# cuisinart-oven.net
KiCad netlist of a schematic drawn in EAGLE
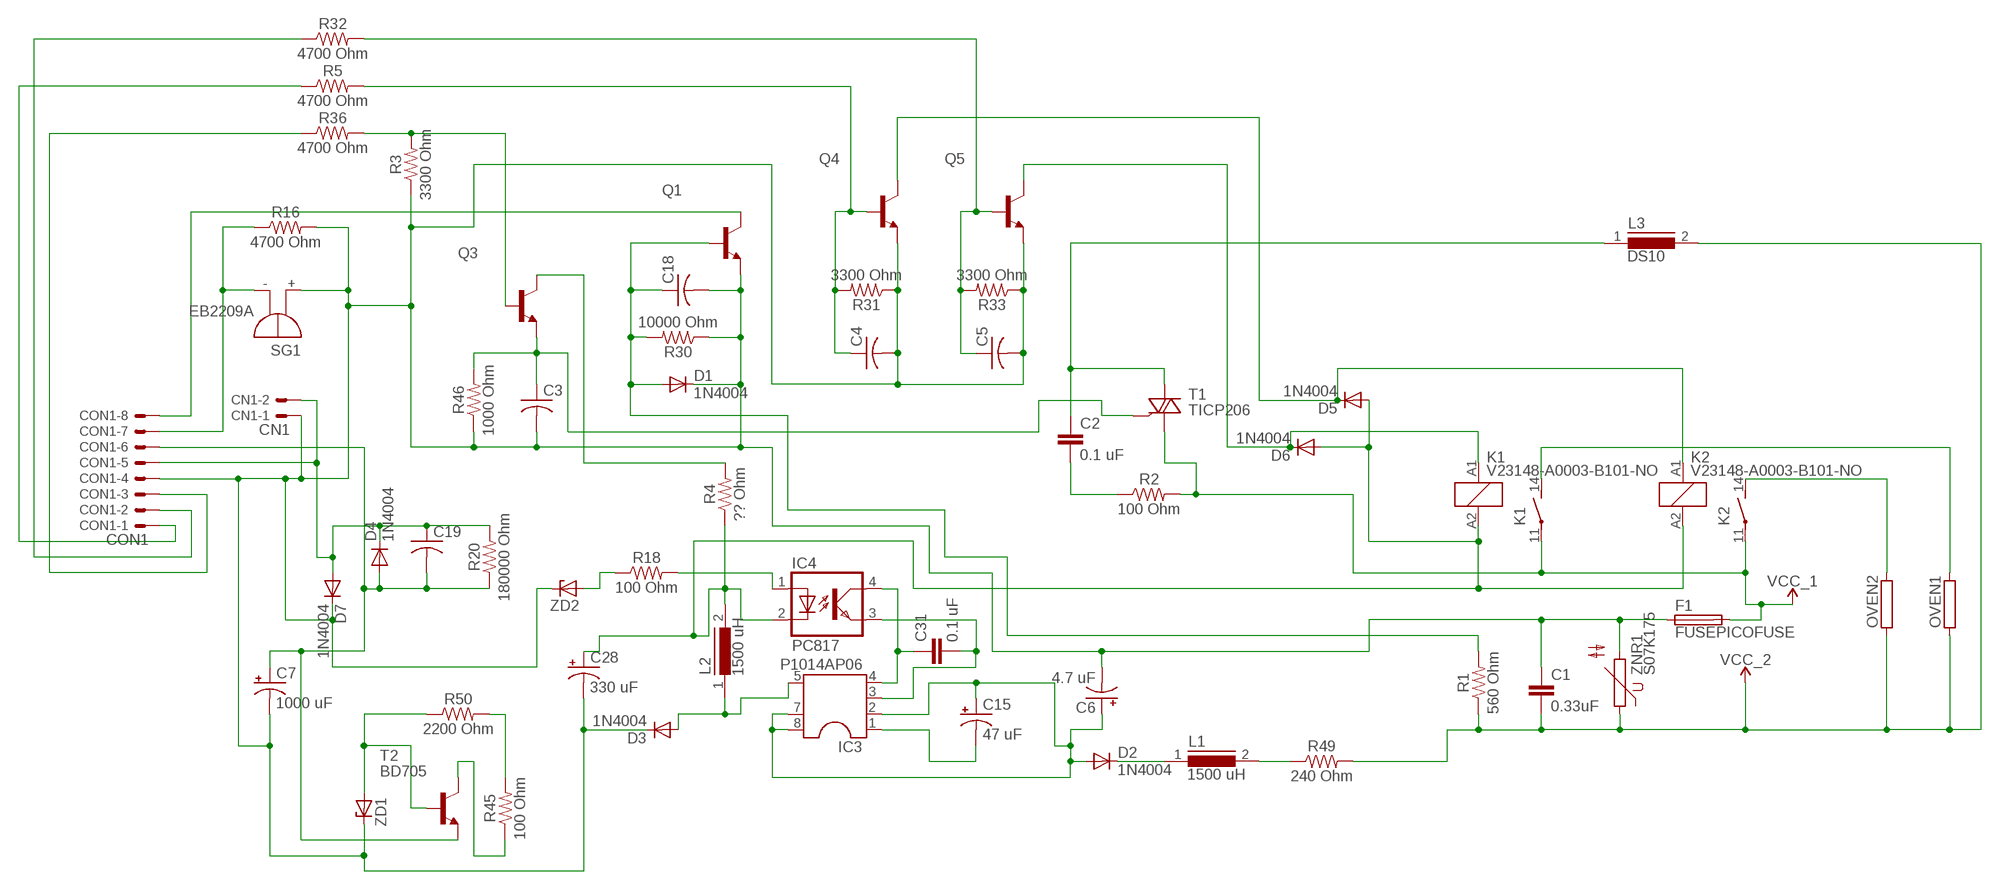
[diagram p0: schematic, sheet 1]

(export (version "E")
  (design (tool "Eeschema 10.0.6"))
  (components
    (comp (ref "C1")
      (value "0.33uF")
      (footprint "eagle-import:C15B9")
      (libsource (lib "eagle-import") (part "C15/9"))
    )
    (comp (ref "C2")
      (value "0.1 uF")
      (footprint "eagle-import:XC15B6")
      (libsource (lib "eagle-import") (part "CXXC15B6"))
    )
    (comp (ref "C3")
      (value "C-US025-024X044")
      (footprint "eagle-import:C025-024X044")
      (libsource (lib "eagle-import") (part "C-US025-024X044"))
    )
    (comp (ref "C4")
      (value "C-US025-024X044")
      (footprint "eagle-import:C025-024X044")
      (libsource (lib "eagle-import") (part "C-US025-024X044"))
    )
    (comp (ref "C5")
      (value "C-US025-024X044")
      (footprint "eagle-import:C025-024X044")
      (libsource (lib "eagle-import") (part "C-US025-024X044"))
    )
    (comp (ref "C6")
      (value "4.7 uF")
      (footprint "eagle-import:E3,5-8")
      (libsource (lib "eagle-import") (part "CPOL-USE3.5-8"))
    )
    (comp (ref "C7")
      (value "1000 uF")
      (footprint "eagle-import:E3,5-8")
      (libsource (lib "eagle-import") (part "CPOL-USE3.5-8"))
    )
    (comp (ref "C15")
      (value "47 uF")
      (footprint "eagle-import:E2-5")
      (libsource (lib "eagle-import") (part "CPOL-USE2-5"))
    )
    (comp (ref "C18")
      (value "C-US025-024X044")
      (footprint "eagle-import:C025-024X044")
      (libsource (lib "eagle-import") (part "C-US025-024X044"))
    )
    (comp (ref "C19")
      (value "C-US025-024X044")
      (footprint "eagle-import:C025-024X044")
      (libsource (lib "eagle-import") (part "C-US025-024X044"))
    )
    (comp (ref "C28")
      (value "330 uF")
      (footprint "eagle-import:E3,5-10")
      (libsource (lib "eagle-import") (part "CPOL-USE3.5-10"))
    )
    (comp (ref "C31")
      (value "0.1 uF")
      (footprint "eagle-import:XC15B6")
      (libsource (lib "eagle-import") (part "CXXC15B6"))
    )
    (comp (ref "CN1")
      (value "CN1")
      (footprint "eagle-import:22-23-2021")
      (fields (field (name "MF") "MOLEX") (field (name "MPN") "22-23-2021"))
      (libsource (lib "eagle-import") (part "22-23-2021"))
    )
    (comp (ref "CON1")
      (value "CON1")
      (footprint "eagle-import:22-23-2081")
      (fields (field (name "MF") "MOLEX") (field (name "MPN") "22-23-2081"))
      (libsource (lib "eagle-import") (part "22-23-2081"))
    )
    (comp (ref "D1")
      (value "1N4004")
      (footprint "eagle-import:DO41-10")
      (libsource (lib "eagle-import") (part "1N4004"))
    )
    (comp (ref "D2")
      (value "1N4004")
      (footprint "eagle-import:DO41-10")
      (libsource (lib "eagle-import") (part "1N4004"))
    )
    (comp (ref "D3")
      (value "1N4004")
      (footprint "eagle-import:DO41-10")
      (libsource (lib "eagle-import") (part "1N4004"))
    )
    (comp (ref "D4")
      (value "1N4004")
      (footprint "eagle-import:DO41-10")
      (libsource (lib "eagle-import") (part "1N4004"))
    )
    (comp (ref "D5")
      (value "1N4004")
      (footprint "eagle-import:DO41-10")
      (libsource (lib "eagle-import") (part "1N4004"))
    )
    (comp (ref "D6")
      (value "1N4004")
      (footprint "eagle-import:DO41-10")
      (libsource (lib "eagle-import") (part "1N4004"))
    )
    (comp (ref "D7")
      (value "1N4004")
      (footprint "eagle-import:DO41-10")
      (libsource (lib "eagle-import") (part "1N4004"))
    )
    (comp (ref "F1")
      (value "FUSEPICOFUSE")
      (footprint "eagle-import:PICOFUSE")
      (libsource (lib "eagle-import") (part "FUSEPICOFUSE"))
    )
    (comp (ref "IC3")
      (value "P1014AP06")
      (footprint "eagle-import:DIP-8B")
      (libsource (lib "eagle-import") (part "TNY267PN"))
    )
    (comp (ref "IC4")
      (value "PC817")
      (footprint "eagle-import:DIL04")
      (fields (field (name "MPN") "PC817X4J000F"))
      (libsource (lib "eagle-import") (part "PC817"))
    )
    (comp (ref "K1")
      (value "V23148-A0003-B101-NO")
      (footprint "eagle-import:V23148-NO")
      (fields (field (name "MPN") "V23148-A0007-A101"))
      (libsource (lib "eagle-import") (part "V23148--NOA0003-B101"))
    )
    (comp (ref "K2")
      (value "V23148-A0003-B101-NO")
      (footprint "eagle-import:V23148-NO")
      (fields (field (name "MPN") "V23148-A0007-A101"))
      (libsource (lib "eagle-import") (part "V23148--NOA0003-B101"))
    )
    (comp (ref "L1")
      (value "1500 uH")
      (footprint "eagle-import:82114R")
      (libsource (lib "eagle-import") (part "82114R"))
    )
    (comp (ref "L2")
      (value "1500 uH")
      (footprint "eagle-import:82114R")
      (libsource (lib "eagle-import") (part "82114R"))
    )
    (comp (ref "L3")
      (value "DS10")
      (footprint "eagle-import:DS10")
      (libsource (lib "eagle-import") (part "DS10"))
    )
    (comp (ref "OVEN1")
      (value "RRWM10X65")
      (footprint "eagle-import:RWM10X65")
      (libsource (lib "eagle-import") (part "RRWM10X65"))
    )
    (comp (ref "OVEN2")
      (value "RRWM10X65")
      (footprint "eagle-import:RWM10X65")
      (libsource (lib "eagle-import") (part "RRWM10X65"))
    )
    (comp (ref "Q1")
      (value "BFS17-NPN-SOT23-BEC")
      (footprint "eagle-import:SOT23-BEC")
      (libsource (lib "eagle-import") (part "-NPN-SOT23-BECBFS17"))
    )
    (comp (ref "Q3")
      (value "BFS17-NPN-SOT23-BEC")
      (footprint "eagle-import:SOT23-BEC")
      (libsource (lib "eagle-import") (part "-NPN-SOT23-BECBFS17"))
    )
    (comp (ref "Q4")
      (value "BFS17-NPN-SOT23-BEC")
      (footprint "eagle-import:SOT23-BEC")
      (libsource (lib "eagle-import") (part "-NPN-SOT23-BECBFS17"))
    )
    (comp (ref "Q5")
      (value "BFS17-NPN-SOT23-BEC")
      (footprint "eagle-import:SOT23-BEC")
      (libsource (lib "eagle-import") (part "-NPN-SOT23-BECBFS17"))
    )
    (comp (ref "R1")
      (value "560 Ohm")
      (footprint "eagle-import:AXIAL-0.3")
      (libsource (lib "eagle-import") (part "RESISTORAXIAL-0.3"))
    )
    (comp (ref "R2")
      (value "100 Ohm")
      (footprint "eagle-import:AXIAL-0.3")
      (libsource (lib "eagle-import") (part "RESISTORAXIAL-0.3"))
    )
    (comp (ref "R3")
      (value "3300 Ohm")
      (footprint "eagle-import:AXIAL-0.3")
      (libsource (lib "eagle-import") (part "RESISTORAXIAL-0.3"))
    )
    (comp (ref "R4")
      (value "?? Ohm")
      (footprint "eagle-import:AXIAL-0.3")
      (libsource (lib "eagle-import") (part "RESISTORAXIAL-0.3"))
    )
    (comp (ref "R5")
      (value "4700 Ohm")
      (footprint "eagle-import:AXIAL-0.3")
      (libsource (lib "eagle-import") (part "RESISTORAXIAL-0.3"))
    )
    (comp (ref "R16")
      (value "4700 Ohm")
      (footprint "eagle-import:AXIAL-0.3")
      (libsource (lib "eagle-import") (part "RESISTORAXIAL-0.3"))
    )
    (comp (ref "R18")
      (value "100 Ohm")
      (footprint "eagle-import:AXIAL-0.3")
      (libsource (lib "eagle-import") (part "RESISTORAXIAL-0.3"))
    )
    (comp (ref "R20")
      (value "180000 Ohm")
      (footprint "eagle-import:AXIAL-0.3")
      (libsource (lib "eagle-import") (part "RESISTORAXIAL-0.3"))
    )
    (comp (ref "R30")
      (value "10000 Ohm")
      (footprint "eagle-import:AXIAL-0.3")
      (libsource (lib "eagle-import") (part "RESISTORAXIAL-0.3"))
    )
    (comp (ref "R31")
      (value "3300 Ohm")
      (footprint "eagle-import:AXIAL-0.3")
      (libsource (lib "eagle-import") (part "RESISTORAXIAL-0.3"))
    )
    (comp (ref "R32")
      (value "4700 Ohm")
      (footprint "eagle-import:AXIAL-0.3")
      (libsource (lib "eagle-import") (part "RESISTORAXIAL-0.3"))
    )
    (comp (ref "R33")
      (value "3300 Ohm")
      (footprint "eagle-import:AXIAL-0.3")
      (libsource (lib "eagle-import") (part "RESISTORAXIAL-0.3"))
    )
    (comp (ref "R36")
      (value "4700 Ohm")
      (footprint "eagle-import:AXIAL-0.3")
      (libsource (lib "eagle-import") (part "RESISTORAXIAL-0.3"))
    )
    (comp (ref "R45")
      (value "100 Ohm")
      (footprint "eagle-import:AXIAL-0.3")
      (libsource (lib "eagle-import") (part "RESISTORAXIAL-0.3"))
    )
    (comp (ref "R46")
      (value "1000 Ohm")
      (footprint "eagle-import:AXIAL-0.3")
      (libsource (lib "eagle-import") (part "RESISTORAXIAL-0.3"))
    )
    (comp (ref "R49")
      (value "240 Ohm")
      (footprint "eagle-import:AXIAL-0.3")
      (libsource (lib "eagle-import") (part "RESISTORAXIAL-0.3"))
    )
    (comp (ref "R50")
      (value "2200 Ohm")
      (footprint "eagle-import:AXIAL-0.3")
      (libsource (lib "eagle-import") (part "RESISTORAXIAL-0.3"))
    )
    (comp (ref "SG1")
      (value "EB2209A")
      (footprint "eagle-import:EB2209A")
      (libsource (lib "eagle-import") (part "EB2209A"))
    )
    (comp (ref "T1")
      (value "TICP206")
      (footprint "eagle-import:TO92-6")
      (libsource (lib "eagle-import") (part "TICP206"))
    )
    (comp (ref "T2")
      (value "BD705")
      (footprint "eagle-import:TO220")
      (libsource (lib "eagle-import") (part "BD705"))
    )
    (comp (ref "ZD1")
      (value "ZENER_DIODEDO41Z10")
      (footprint "eagle-import:DO41Z10")
      (libsource (lib "eagle-import") (part "ZENER_DIODEDO41Z10"))
    )
    (comp (ref "ZD2")
      (value "ZENER_DIODEDO41Z10")
      (footprint "eagle-import:DO41Z10")
      (libsource (lib "eagle-import") (part "ZENER_DIODEDO41Z10"))
    )
    (comp (ref "ZNR1")
      (value "S07K175")
      (footprint "eagle-import:S07K175")
      (libsource (lib "eagle-import") (part "S07K175"))
    )
  )
  (nets
    (net (code "1") (name "Net-(C2-Pad1)") (class "Default")
      (node (ref "C2") (pin "1") (pinfunction "1_1") (pintype "passive"))
      (node (ref "L3") (pin "1") (pinfunction "1_1") (pintype "passive"))
      (node (ref "T1") (pin "A2") (pinfunction "A2_A2") (pintype "passive"))
    )
    (net (code "2") (name "Net-(CN1A-S)") (class "Default")
      (node (ref "C1") (pin "1") (pinfunction "1_1") (pintype "passive"))
      (node (ref "C18") (pin "2") (pinfunction "2_2") (pintype "passive"))
      (node (ref "C28") (pin "-") (pinfunction "-_-") (pintype "passive"))
      (node (ref "C3") (pin "2") (pinfunction "2_2") (pintype "passive"))
      (node (ref "C4") (pin "2") (pinfunction "2_2") (pintype "passive"))
      (node (ref "C5") (pin "2") (pinfunction "2_2") (pintype "passive"))
      (node (ref "C6") (pin "-") (pinfunction "-_-") (pintype "passive"))
      (node (ref "C7") (pin "-") (pinfunction "-_-") (pintype "passive"))
      (node (ref "CN1") (pin "1") (pinfunction "S_1") (pintype "passive"))
      (node (ref "CON1") (pin "4") (pinfunction "S_4") (pintype "passive"))
      (node (ref "D1") (pin "C") (pinfunction "C_C") (pintype "passive"))
      (node (ref "D3") (pin "C") (pinfunction "C_C") (pintype "passive"))
      (node (ref "D7") (pin "C") (pinfunction "C_C") (pintype "passive"))
      (node (ref "F1") (pin "1") (pinfunction "1_1") (pintype "passive"))
      (node (ref "Q1") (pin "E") (pinfunction "E_E") (pintype "passive"))
      (node (ref "Q4") (pin "E") (pinfunction "E_E") (pintype "passive"))
      (node (ref "Q5") (pin "E") (pinfunction "E_E") (pintype "passive"))
      (node (ref "R16") (pin "P$2") (pinfunction "2_P$2") (pintype "passive"))
      (node (ref "R3") (pin "P$1") (pinfunction "1_P$1") (pintype "passive"))
      (node (ref "R30") (pin "P$1") (pinfunction "1_P$1") (pintype "passive"))
      (node (ref "R31") (pin "P$1") (pinfunction "1_P$1") (pintype "passive"))
      (node (ref "R33") (pin "P$1") (pinfunction "1_P$1") (pintype "passive"))
      (node (ref "R46") (pin "P$1") (pinfunction "1_P$1") (pintype "passive"))
      (node (ref "SG1") (pin "+") (pinfunction "+_+") (pintype "passive"))
      (node (ref "ZD1") (pin "C") (pinfunction "CATHODE_C") (pintype "passive"))
      (node (ref "ZD2") (pin "C") (pinfunction "CATHODE_C") (pintype "passive"))
      (node (ref "ZNR1") (pin "2") (pinfunction "2_2") (pintype "passive"))
    )
    (net (code "3") (name "Net-(CN1B-S)") (class "Default")
      (node (ref "C19") (pin "1") (pinfunction "1_1") (pintype "passive"))
      (node (ref "CN1") (pin "2") (pinfunction "S_2") (pintype "passive"))
      (node (ref "CON1") (pin "5") (pinfunction "S_5") (pintype "passive"))
      (node (ref "D4") (pin "C") (pinfunction "C_C") (pintype "passive"))
      (node (ref "D7") (pin "A") (pinfunction "A_A") (pintype "passive"))
      (node (ref "R20") (pin "P$2") (pinfunction "2_P$2") (pintype "passive"))
    )
    (net (code "4") (name "Net-(CON1A-S)") (class "Default")
      (node (ref "CON1") (pin "1") (pinfunction "S_1") (pintype "passive"))
      (node (ref "R5") (pin "P$1") (pinfunction "1_P$1") (pintype "passive"))
    )
    (net (code "5") (name "Net-(CON1B-S)") (class "Default")
      (node (ref "CON1") (pin "2") (pinfunction "S_2") (pintype "passive"))
      (node (ref "R32") (pin "P$1") (pinfunction "1_P$1") (pintype "passive"))
    )
    (net (code "6") (name "Net-(CON1C-S)") (class "Default")
      (node (ref "CON1") (pin "3") (pinfunction "S_3") (pintype "passive"))
      (node (ref "R36") (pin "P$1") (pinfunction "1_P$1") (pintype "passive"))
    )
    (net (code "7") (name "Net-(CON1F-S)") (class "Default")
      (node (ref "C19") (pin "2") (pinfunction "2_2") (pintype "passive"))
      (node (ref "C7") (pin "+") (pinfunction "+_+") (pintype "passive"))
      (node (ref "CON1") (pin "6") (pinfunction "S_6") (pintype "passive"))
      (node (ref "D4") (pin "A") (pinfunction "A_A") (pintype "passive"))
      (node (ref "R20") (pin "P$1") (pinfunction "1_P$1") (pintype "passive"))
      (node (ref "T2") (pin "3") (pinfunction "E_3") (pintype "passive"))
    )
    (net (code "8") (name "Net-(CON1G-S)") (class "Default")
      (node (ref "CON1") (pin "7") (pinfunction "S_7") (pintype "passive"))
      (node (ref "R16") (pin "P$1") (pinfunction "1_P$1") (pintype "passive"))
      (node (ref "SG1") (pin "-") (pinfunction "-_-") (pintype "passive"))
    )
    (net (code "9") (name "Net-(CON1H-S)") (class "Default")
      (node (ref "CON1") (pin "8") (pinfunction "S_8") (pintype "passive"))
      (node (ref "Q1") (pin "C") (pinfunction "C_C") (pintype "passive"))
    )
    (net (code "10") (name "Net-(D2-PadC)") (class "Default")
      (node (ref "D2") (pin "C") (pinfunction "C_C") (pintype "passive"))
      (node (ref "L1") (pin "1") (pinfunction "1_1") (pintype "passive"))
    )
    (net (code "11") (name "Net-(IC3-2GND)") (class "Default")
      (node (ref "C15") (pin "+") (pinfunction "+_+") (pintype "passive"))
      (node (ref "C6") (pin "+") (pinfunction "+_+") (pintype "passive"))
      (node (ref "D2") (pin "A") (pinfunction "A_A") (pintype "passive"))
      (node (ref "IC3") (pin "2") (pinfunction "2GND_2") (pintype "passive"))
      (node (ref "IC3") (pin "7") (pinfunction "7HV-GND_7") (pintype "passive"))
      (node (ref "IC3") (pin "8") (pinfunction "8HV-GND_8") (pintype "passive"))
    )
    (net (code "12") (name "Net-(IC3-3GND)") (class "Default")
      (node (ref "C31") (pin "2") (pinfunction "2_2") (pintype "passive"))
      (node (ref "IC3") (pin "3") (pinfunction "3GND_3") (pintype "passive"))
      (node (ref "IC4") (pin "3") (pinfunction "EMIT_3") (pintype "passive"))
    )
    (net (code "13") (name "Net-(IC3-BP)") (class "Default")
      (node (ref "C15") (pin "-") (pinfunction "-_-") (pintype "passive"))
      (node (ref "IC3") (pin "1") (pinfunction "BP_1") (pintype "passive"))
    )
    (net (code "14") (name "Net-(IC3-D)") (class "Default")
      (node (ref "D3") (pin "A") (pinfunction "A_A") (pintype "passive"))
      (node (ref "IC3") (pin "5") (pinfunction "D_5") (pintype "passive"))
      (node (ref "L2") (pin "1") (pinfunction "1_1") (pintype "passive"))
    )
    (net (code "15") (name "Net-(IC3-EN{slash}UV)") (class "Default")
      (node (ref "C31") (pin "1") (pinfunction "1_1") (pintype "passive"))
      (node (ref "IC3") (pin "4") (pinfunction "EN/UV_4") (pintype "passive"))
      (node (ref "IC4") (pin "4") (pinfunction "COL_4") (pintype "passive"))
    )
    (net (code "16") (name "Net-(IC4-A)") (class "Default")
      (node (ref "IC4") (pin "1") (pinfunction "A_1") (pintype "passive"))
      (node (ref "R18") (pin "P$2") (pinfunction "2_P$2") (pintype "passive"))
    )
    (net (code "17") (name "Net-(IC4-C)") (class "Default")
      (node (ref "C28") (pin "+") (pinfunction "+_+") (pintype "passive"))
      (node (ref "D5") (pin "A") (pinfunction "A_A") (pintype "passive"))
      (node (ref "D6") (pin "A") (pinfunction "A_A") (pintype "passive"))
      (node (ref "IC4") (pin "2") (pinfunction "C_2") (pintype "passive"))
      (node (ref "K1") (pin "A2") (pinfunction "2_A2") (pintype "passive"))
      (node (ref "K2") (pin "A2") (pinfunction "2_A2") (pintype "passive"))
      (node (ref "L2") (pin "2") (pinfunction "2_2") (pintype "passive"))
      (node (ref "R4") (pin "P$1") (pinfunction "1_P$1") (pintype "passive"))
    )
    (net (code "18") (name "Net-(K1A-1)") (class "Default")
      (node (ref "D6") (pin "C") (pinfunction "C_C") (pintype "passive"))
      (node (ref "K1") (pin "A1") (pinfunction "1_A1") (pintype "passive"))
      (node (ref "Q5") (pin "C") (pinfunction "C_C") (pintype "passive"))
    )
    (net (code "19") (name "Net-(K1B-S)") (class "Default")
      (node (ref "K1") (pin "14") (pinfunction "S_14") (pintype "passive"))
      (node (ref "OVEN1") (pin "2") (pinfunction "2_2") (pintype "passive"))
    )
    (net (code "20") (name "Net-(K2A-1)") (class "Default")
      (node (ref "D5") (pin "C") (pinfunction "C_C") (pintype "passive"))
      (node (ref "K2") (pin "A1") (pinfunction "1_A1") (pintype "passive"))
      (node (ref "Q4") (pin "C") (pinfunction "C_C") (pintype "passive"))
    )
    (net (code "21") (name "Net-(K2B-S)") (class "Default")
      (node (ref "K2") (pin "14") (pinfunction "S_14") (pintype "passive"))
      (node (ref "OVEN2") (pin "2") (pinfunction "2_2") (pintype "passive"))
    )
    (net (code "22") (name "Net-(R1-2)") (class "Default")
      (node (ref "C18") (pin "1") (pinfunction "1_1") (pintype "passive"))
      (node (ref "D1") (pin "A") (pinfunction "A_A") (pintype "passive"))
      (node (ref "Q1") (pin "B") (pinfunction "B_B") (pintype "passive"))
      (node (ref "R1") (pin "P$2") (pinfunction "2_P$2") (pintype "passive"))
      (node (ref "R30") (pin "P$2") (pinfunction "2_P$2") (pintype "passive"))
    )
    (net (code "23") (name "Net-(R2-1)") (class "Default")
      (node (ref "C2") (pin "2") (pinfunction "2_2") (pintype "passive"))
      (node (ref "R2") (pin "P$1") (pinfunction "1_P$1") (pintype "passive"))
    )
    (net (code "24") (name "Net-(R3-2)") (class "Default")
      (node (ref "Q3") (pin "B") (pinfunction "B_B") (pintype "passive"))
      (node (ref "R3") (pin "P$2") (pinfunction "2_P$2") (pintype "passive"))
      (node (ref "R36") (pin "P$2") (pinfunction "2_P$2") (pintype "passive"))
    )
    (net (code "25") (name "Net-(R4-2)") (class "Default")
      (node (ref "Q3") (pin "C") (pinfunction "C_C") (pintype "passive"))
      (node (ref "R4") (pin "P$2") (pinfunction "2_P$2") (pintype "passive"))
    )
    (net (code "26") (name "Net-(R18-1)") (class "Default")
      (node (ref "R18") (pin "P$1") (pinfunction "1_P$1") (pintype "passive"))
      (node (ref "ZD2") (pin "A") (pinfunction "ANODE_A") (pintype "passive"))
    )
    (net (code "27") (name "Net-(R31-2)") (class "Default")
      (node (ref "C4") (pin "1") (pinfunction "1_1") (pintype "passive"))
      (node (ref "Q4") (pin "B") (pinfunction "B_B") (pintype "passive"))
      (node (ref "R31") (pin "P$2") (pinfunction "2_P$2") (pintype "passive"))
      (node (ref "R5") (pin "P$2") (pinfunction "2_P$2") (pintype "passive"))
    )
    (net (code "28") (name "Net-(R32-2)") (class "Default")
      (node (ref "C5") (pin "1") (pinfunction "1_1") (pintype "passive"))
      (node (ref "Q5") (pin "B") (pinfunction "B_B") (pintype "passive"))
      (node (ref "R32") (pin "P$2") (pinfunction "2_P$2") (pintype "passive"))
      (node (ref "R33") (pin "P$2") (pinfunction "2_P$2") (pintype "passive"))
    )
    (net (code "29") (name "Net-(R45-1)") (class "Default")
      (node (ref "R45") (pin "P$1") (pinfunction "1_P$1") (pintype "passive"))
      (node (ref "T2") (pin "2") (pinfunction "C_2") (pintype "passive"))
    )
    (net (code "30") (name "Net-(R45-2)") (class "Default")
      (node (ref "R45") (pin "P$2") (pinfunction "2_P$2") (pintype "passive"))
      (node (ref "R50") (pin "P$2") (pinfunction "2_P$2") (pintype "passive"))
    )
    (net (code "31") (name "Net-(R46-2)") (class "Default")
      (node (ref "C3") (pin "1") (pinfunction "1_1") (pintype "passive"))
      (node (ref "Q3") (pin "E") (pinfunction "E_E") (pintype "passive"))
      (node (ref "R46") (pin "P$2") (pinfunction "2_P$2") (pintype "passive"))
      (node (ref "T1") (pin "G") (pinfunction "G_G") (pintype "passive"))
    )
    (net (code "32") (name "Net-(R49-1)") (class "Default")
      (node (ref "L1") (pin "2") (pinfunction "2_2") (pintype "passive"))
      (node (ref "R49") (pin "P$1") (pinfunction "1_P$1") (pintype "passive"))
    )
    (net (code "33") (name "Net-(R50-1)") (class "Default")
      (node (ref "R50") (pin "P$1") (pinfunction "1_P$1") (pintype "passive"))
      (node (ref "T2") (pin "1") (pinfunction "B_1") (pintype "passive"))
      (node (ref "ZD1") (pin "A") (pinfunction "ANODE_A") (pintype "passive"))
    )
    (net (code "34") (name "VCC_1") (class "Default")
      (node (ref "F1") (pin "2") (pinfunction "2_2") (pintype "passive"))
      (node (ref "K1") (pin "11") (pinfunction "P_11") (pintype "passive"))
      (node (ref "K2") (pin "11") (pinfunction "P_11") (pintype "passive"))
      (node (ref "R2") (pin "P$2") (pinfunction "2_P$2") (pintype "passive"))
      (node (ref "T1") (pin "A1") (pinfunction "A1_A1") (pintype "passive"))
    )
    (net (code "35") (name "VCC_2") (class "Default")
      (node (ref "C1") (pin "2") (pinfunction "2_2") (pintype "passive"))
      (node (ref "L3") (pin "2") (pinfunction "2_2") (pintype "passive"))
      (node (ref "OVEN1") (pin "1") (pinfunction "1_1") (pintype "passive"))
      (node (ref "OVEN2") (pin "1") (pinfunction "1_1") (pintype "passive"))
      (node (ref "R1") (pin "P$1") (pinfunction "1_P$1") (pintype "passive"))
      (node (ref "R49") (pin "P$2") (pinfunction "2_P$2") (pintype "passive"))
      (node (ref "ZNR1") (pin "1") (pinfunction "1_1") (pintype "passive"))
    )
  )
)
